# axon_revB.net
KiCad netlist of a schematic drawn in EAGLE
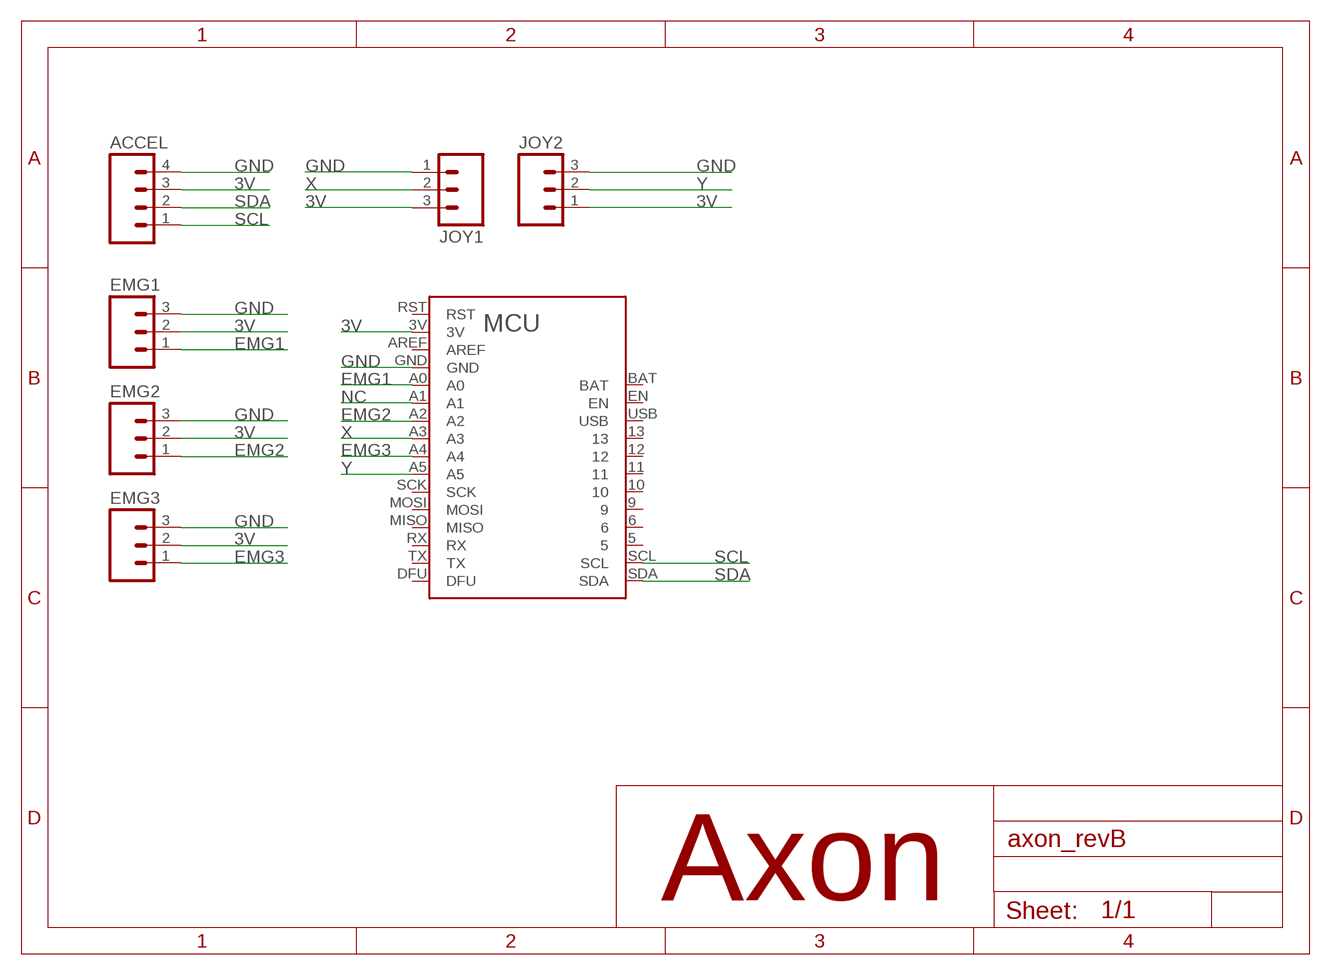
[diagram p0: schematic, sheet 1]

(export (version "E")
  (design (tool "Eeschema 10.0.6"))
  (components
    (comp (ref "ACCEL")
      (value "M04POLAR")
      (footprint "eagle-import:MOLEX-1X4")
      (libsource (lib "eagle-import") (part "M04POLAR"))
    )
    (comp (ref "EMG1")
      (value "M03POLAR")
      (footprint "eagle-import:MOLEX-1X3")
      (libsource (lib "eagle-import") (part "M03POLAR"))
    )
    (comp (ref "EMG2")
      (value "M03POLAR")
      (footprint "eagle-import:MOLEX-1X3")
      (libsource (lib "eagle-import") (part "M03POLAR"))
    )
    (comp (ref "EMG3")
      (value "M03POLAR")
      (footprint "eagle-import:MOLEX-1X3")
      (libsource (lib "eagle-import") (part "M03POLAR"))
    )
    (comp (ref "JOY1")
      (value "M03PTH")
      (footprint "eagle-import:1X03")
      (libsource (lib "eagle-import") (part "M03PTH"))
    )
    (comp (ref "JOY2")
      (value "M03PTH")
      (footprint "eagle-import:1X03")
      (libsource (lib "eagle-import") (part "M03PTH"))
    )
    (comp (ref "MCU")
      (value "BLUEFRUIT")
      (footprint "eagle-import:BLUEFRUIT")
      (libsource (lib "eagle-import") (part "BLUEFRUIT"))
    )
  )
  (nets
    (net (code "1") (name "/3V") (class "Default")
      (node (ref "ACCEL") (pin "3") (pinfunction "3_3") (pintype "passive"))
      (node (ref "EMG1") (pin "2") (pinfunction "2_2") (pintype "passive"))
      (node (ref "EMG2") (pin "2") (pinfunction "2_2") (pintype "passive"))
      (node (ref "EMG3") (pin "2") (pinfunction "2_2") (pintype "passive"))
      (node (ref "JOY1") (pin "3") (pinfunction "3_3") (pintype "passive"))
      (node (ref "JOY2") (pin "1") (pinfunction "1_1") (pintype "passive"))
      (node (ref "MCU") (pin "3V") (pinfunction "3V_3V") (pintype "power_in"))
    )
    (net (code "2") (name "/EMG1") (class "Default")
      (node (ref "EMG1") (pin "1") (pinfunction "1_1") (pintype "passive"))
      (node (ref "MCU") (pin "A0") (pinfunction "A0_A0") (pintype "bidirectional"))
    )
    (net (code "3") (name "/EMG2") (class "Default")
      (node (ref "EMG2") (pin "1") (pinfunction "1_1") (pintype "passive"))
      (node (ref "MCU") (pin "A2") (pinfunction "A2_A2") (pintype "bidirectional"))
    )
    (net (code "4") (name "/EMG3") (class "Default")
      (node (ref "EMG3") (pin "1") (pinfunction "1_1") (pintype "passive"))
      (node (ref "MCU") (pin "A4") (pinfunction "A4_A4") (pintype "bidirectional"))
    )
    (net (code "5") (name "/GND") (class "Default")
      (node (ref "ACCEL") (pin "4") (pinfunction "4_4") (pintype "passive"))
      (node (ref "EMG1") (pin "3") (pinfunction "3_3") (pintype "passive"))
      (node (ref "EMG2") (pin "3") (pinfunction "3_3") (pintype "passive"))
      (node (ref "EMG3") (pin "3") (pinfunction "3_3") (pintype "passive"))
      (node (ref "JOY1") (pin "1") (pinfunction "1_1") (pintype "passive"))
      (node (ref "JOY2") (pin "3") (pinfunction "3_3") (pintype "passive"))
      (node (ref "MCU") (pin "GND") (pinfunction "GND_GND") (pintype "power_in"))
    )
    (net (code "6") (name "/NC") (class "Default")
      (node (ref "MCU") (pin "A1") (pinfunction "A1_A1") (pintype "bidirectional"))
    )
    (net (code "7") (name "/SCL") (class "Default")
      (node (ref "ACCEL") (pin "1") (pinfunction "1_1") (pintype "passive"))
      (node (ref "MCU") (pin "SCL") (pinfunction "SCL_SCL") (pintype "bidirectional"))
    )
    (net (code "8") (name "/SDA") (class "Default")
      (node (ref "ACCEL") (pin "2") (pinfunction "2_2") (pintype "passive"))
      (node (ref "MCU") (pin "SDA") (pinfunction "SDA_SDA") (pintype "bidirectional"))
    )
    (net (code "9") (name "/X") (class "Default")
      (node (ref "JOY1") (pin "2") (pinfunction "2_2") (pintype "passive"))
      (node (ref "MCU") (pin "A3") (pinfunction "A3_A3") (pintype "bidirectional"))
    )
    (net (code "10") (name "/Y") (class "Default")
      (node (ref "JOY2") (pin "2") (pinfunction "2_2") (pintype "passive"))
      (node (ref "MCU") (pin "A5") (pinfunction "A5_A5") (pintype "bidirectional"))
    )
    (net (code "11") (name "unconnected-(MCU-Pad5)") (class "Default")
      (node (ref "MCU") (pin "5") (pinfunction "5_5") (pintype "bidirectional"))
    )
    (net (code "12") (name "unconnected-(MCU-Pad6)") (class "Default")
      (node (ref "MCU") (pin "6") (pinfunction "6_6") (pintype "bidirectional"))
    )
    (net (code "13") (name "unconnected-(MCU-Pad9)") (class "Default")
      (node (ref "MCU") (pin "9") (pinfunction "9_9") (pintype "bidirectional"))
    )
    (net (code "14") (name "unconnected-(MCU-Pad10)") (class "Default")
      (node (ref "MCU") (pin "10") (pinfunction "10_10") (pintype "bidirectional"))
    )
    (net (code "15") (name "unconnected-(MCU-Pad11)") (class "Default")
      (node (ref "MCU") (pin "11") (pinfunction "11_11") (pintype "bidirectional"))
    )
    (net (code "16") (name "unconnected-(MCU-Pad12)") (class "Default")
      (node (ref "MCU") (pin "12") (pinfunction "12_12") (pintype "bidirectional"))
    )
    (net (code "17") (name "unconnected-(MCU-Pad13)") (class "Default")
      (node (ref "MCU") (pin "13") (pinfunction "13_13") (pintype "bidirectional"))
    )
    (net (code "18") (name "unconnected-(MCU-PadAREF)") (class "Default")
      (node (ref "MCU") (pin "AREF") (pinfunction "AREF_AREF") (pintype "bidirectional"))
    )
    (net (code "19") (name "unconnected-(MCU-PadBAT)") (class "Default")
      (node (ref "MCU") (pin "BAT") (pinfunction "BAT_BAT") (pintype "bidirectional"))
    )
    (net (code "20") (name "unconnected-(MCU-PadDFU)") (class "Default")
      (node (ref "MCU") (pin "DFU") (pinfunction "DFU_DFU") (pintype "bidirectional"))
    )
    (net (code "21") (name "unconnected-(MCU-PadEN)") (class "Default")
      (node (ref "MCU") (pin "EN") (pinfunction "EN_EN") (pintype "bidirectional"))
    )
    (net (code "22") (name "unconnected-(MCU-PadMISO)") (class "Default")
      (node (ref "MCU") (pin "MISO") (pinfunction "MISO_MISO") (pintype "bidirectional"))
    )
    (net (code "23") (name "unconnected-(MCU-PadMOSI)") (class "Default")
      (node (ref "MCU") (pin "MOSI") (pinfunction "MOSI_MOSI") (pintype "bidirectional"))
    )
    (net (code "24") (name "unconnected-(MCU-PadRST)") (class "Default")
      (node (ref "MCU") (pin "RST") (pinfunction "RST_RST") (pintype "bidirectional"))
    )
    (net (code "25") (name "unconnected-(MCU-PadRX)") (class "Default")
      (node (ref "MCU") (pin "RX") (pinfunction "RX_RX") (pintype "bidirectional"))
    )
    (net (code "26") (name "unconnected-(MCU-PadSCK)") (class "Default")
      (node (ref "MCU") (pin "SCK") (pinfunction "SCK_SCK") (pintype "bidirectional"))
    )
    (net (code "27") (name "unconnected-(MCU-PadTX)") (class "Default")
      (node (ref "MCU") (pin "TX") (pinfunction "TX_TX") (pintype "bidirectional"))
    )
    (net (code "28") (name "unconnected-(MCU-PadUSB)") (class "Default")
      (node (ref "MCU") (pin "USB") (pinfunction "USB_USB") (pintype "bidirectional"))
    )
  )
)
